# gpio4p2.net
KiCad netlist of a schematic drawn in EAGLE
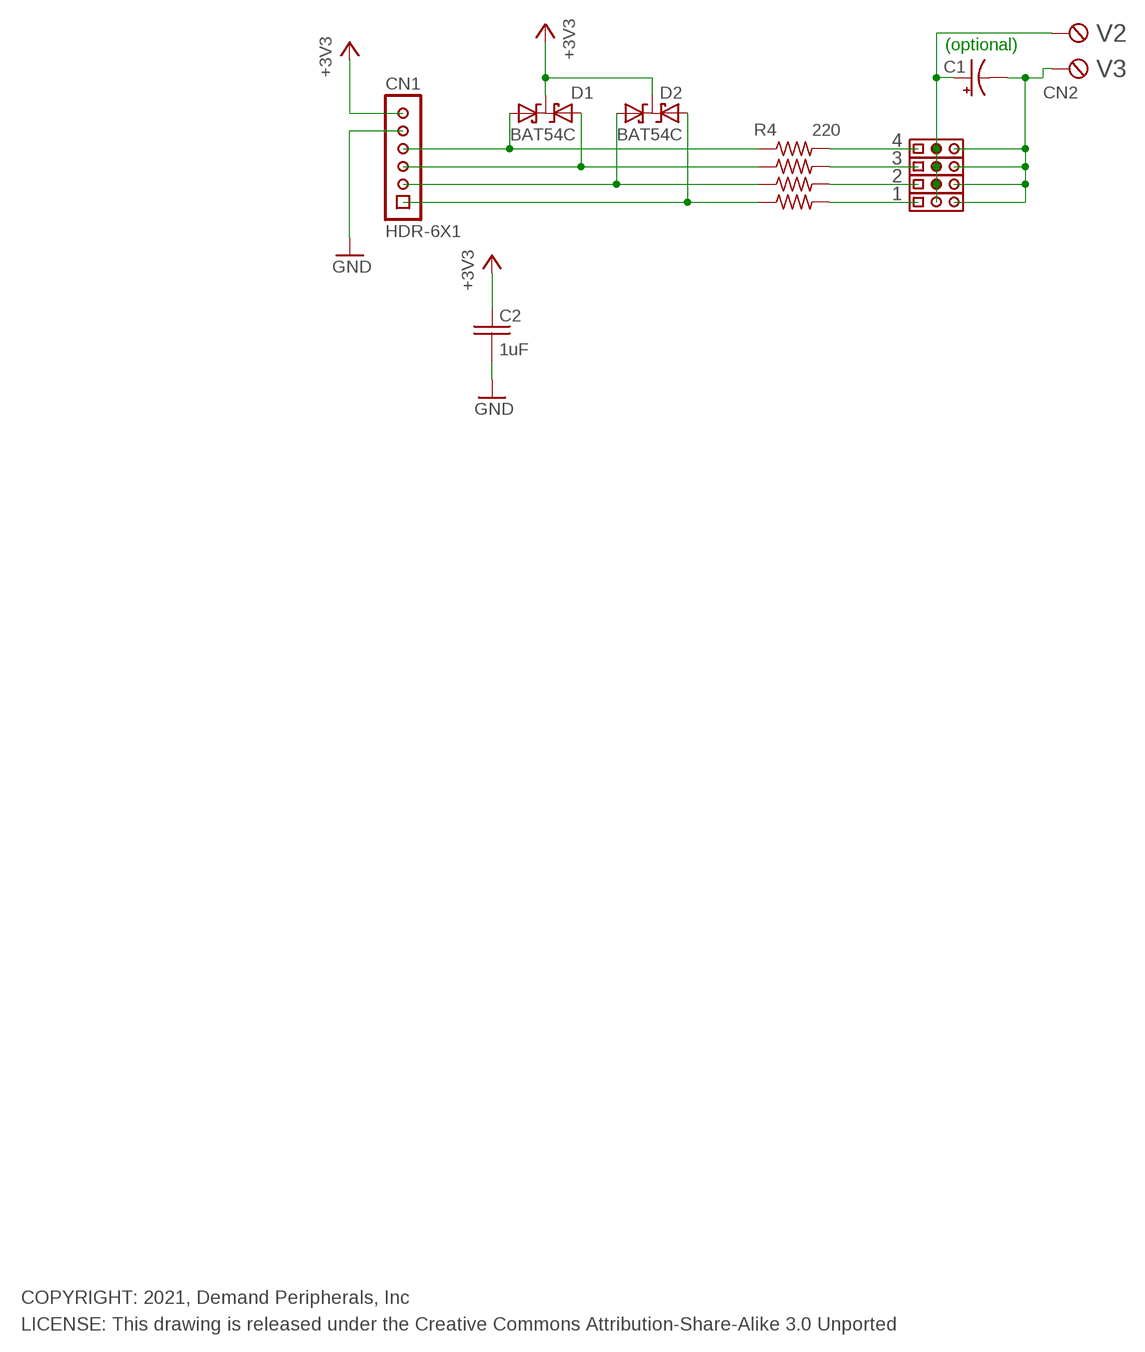
[diagram p0: schematic, sheet 1]

(export (version "E")
  (design (tool "Eeschema 10.0.6"))
  (components
    (comp (ref "C1")
      (value "100uF")
      (footprint "eagle-import:E3.5-8")
      (libsource (lib "eagle-import") (part "C100UF_E3.5-8"))
    )
    (comp (ref "C2")
      (value "1uF")
      (footprint "eagle-import:C0603")
      (libsource (lib "eagle-import") (part "C1.0UF_C0603"))
    )
    (comp (ref "CN1")
      (value "HDR-6X1")
      (footprint "eagle-import:HDR-6X1")
      (libsource (lib "eagle-import") (part "HDR-6X1"))
    )
    (comp (ref "CN2")
      (value "TBLK-5.08-X2")
      (footprint "eagle-import:TBLK-5.08-X2")
      (libsource (lib "eagle-import") (part "TBLK-5.08-X2"))
    )
    (comp (ref "D1")
      (value "BAT54C")
      (footprint "eagle-import:SOT23")
      (libsource (lib "eagle-import") (part "BAT54C"))
    )
    (comp (ref "D2")
      (value "BAT54C")
      (footprint "eagle-import:SOT23")
      (libsource (lib "eagle-import") (part "BAT54C"))
    )
    (comp (ref "R1")
      (value "220")
      (footprint "eagle-import:R0603")
      (libsource (lib "eagle-import") (part "R220_R0603"))
    )
    (comp (ref "R2")
      (value "220")
      (footprint "eagle-import:R0603")
      (libsource (lib "eagle-import") (part "R220_R0603"))
    )
    (comp (ref "R3")
      (value "220")
      (footprint "eagle-import:R0603")
      (libsource (lib "eagle-import") (part "R220_R0603"))
    )
    (comp (ref "R4")
      (value "220")
      (footprint "eagle-import:R0603")
      (libsource (lib "eagle-import") (part "R220_R0603"))
    )
    (comp (ref "U$5")
      (value "HDR-3X1")
      (footprint "eagle-import:HDR-3X1")
      (libsource (lib "eagle-import") (part "HDR-3X1"))
    )
    (comp (ref "U$6")
      (value "HDR-3X1")
      (footprint "eagle-import:HDR-3X1")
      (libsource (lib "eagle-import") (part "HDR-3X1"))
    )
    (comp (ref "U$7")
      (value "HDR-3X1")
      (footprint "eagle-import:HDR-3X1")
      (libsource (lib "eagle-import") (part "HDR-3X1"))
    )
    (comp (ref "U$9")
      (value "HDR-3X1")
      (footprint "eagle-import:HDR-3X1")
      (libsource (lib "eagle-import") (part "HDR-3X1"))
    )
  )
  (nets
    (net (code "1") (name "+3V3") (class "Default")
      (node (ref "C2") (pin "1") (pinfunction "1_1") (pintype "passive"))
      (node (ref "CN1") (pin "6") (pinfunction "6_6") (pintype "passive"))
      (node (ref "D1") (pin "3") (pinfunction "CC_3") (pintype "passive"))
      (node (ref "D2") (pin "3") (pinfunction "CC_3") (pintype "passive"))
    )
    (net (code "2") (name "GND") (class "Default")
      (node (ref "C2") (pin "2") (pinfunction "2_2") (pintype "passive"))
      (node (ref "CN1") (pin "5") (pinfunction "5_5") (pintype "passive"))
    )
    (net (code "3") (name "Net-(CN2-KL)") (class "Default")
      (node (ref "C1") (pin "-") (pinfunction "-_-") (pintype "passive"))
      (node (ref "CN2") (pin "1") (pinfunction "KL_1") (pintype "passive"))
      (node (ref "U$5") (pin "3") (pinfunction "3_3") (pintype "passive"))
      (node (ref "U$6") (pin "3") (pinfunction "3_3") (pintype "passive"))
      (node (ref "U$7") (pin "3") (pinfunction "3_3") (pintype "passive"))
      (node (ref "U$9") (pin "3") (pinfunction "3_3") (pintype "passive"))
    )
    (net (code "4") (name "Net-(CN2-KL1)") (class "Default")
      (node (ref "C1") (pin "+") (pinfunction "+_+") (pintype "passive"))
      (node (ref "CN2") (pin "2") (pinfunction "KL1_2") (pintype "passive"))
      (node (ref "U$5") (pin "2") (pinfunction "2_2") (pintype "passive"))
      (node (ref "U$6") (pin "2") (pinfunction "2_2") (pintype "passive"))
      (node (ref "U$7") (pin "2") (pinfunction "2_2") (pintype "passive"))
      (node (ref "U$9") (pin "2") (pinfunction "2_2") (pintype "passive"))
    )
    (net (code "5") (name "Net-(D1-A)") (class "Default")
      (node (ref "CN1") (pin "4") (pinfunction "4_4") (pintype "passive"))
      (node (ref "D1") (pin "2") (pinfunction "A_2") (pintype "passive"))
      (node (ref "R4") (pin "1") (pinfunction "1_1") (pintype "passive"))
    )
    (net (code "6") (name "Net-(D1-A1)") (class "Default")
      (node (ref "CN1") (pin "3") (pinfunction "3_3") (pintype "passive"))
      (node (ref "D1") (pin "1") (pinfunction "A1_1") (pintype "passive"))
      (node (ref "R3") (pin "1") (pinfunction "1_1") (pintype "passive"))
    )
    (net (code "7") (name "Net-(D2-A)") (class "Default")
      (node (ref "CN1") (pin "2") (pinfunction "2_2") (pintype "passive"))
      (node (ref "D2") (pin "2") (pinfunction "A_2") (pintype "passive"))
      (node (ref "R2") (pin "1") (pinfunction "1_1") (pintype "passive"))
    )
    (net (code "8") (name "Net-(D2-A1)") (class "Default")
      (node (ref "CN1") (pin "1") (pinfunction "1_1") (pintype "passive"))
      (node (ref "D2") (pin "1") (pinfunction "A1_1") (pintype "passive"))
      (node (ref "R1") (pin "1") (pinfunction "1_1") (pintype "passive"))
    )
    (net (code "9") (name "Net-(R1-Pad2)") (class "Default")
      (node (ref "R1") (pin "2") (pinfunction "2_2") (pintype "passive"))
      (node (ref "U$9") (pin "1") (pinfunction "1_1") (pintype "passive"))
    )
    (net (code "10") (name "Net-(R2-Pad2)") (class "Default")
      (node (ref "R2") (pin "2") (pinfunction "2_2") (pintype "passive"))
      (node (ref "U$7") (pin "1") (pinfunction "1_1") (pintype "passive"))
    )
    (net (code "11") (name "Net-(R3-Pad2)") (class "Default")
      (node (ref "R3") (pin "2") (pinfunction "2_2") (pintype "passive"))
      (node (ref "U$6") (pin "1") (pinfunction "1_1") (pintype "passive"))
    )
    (net (code "12") (name "Net-(R4-Pad2)") (class "Default")
      (node (ref "R4") (pin "2") (pinfunction "2_2") (pintype "passive"))
      (node (ref "U$5") (pin "1") (pinfunction "1_1") (pintype "passive"))
    )
  )
)
